# PCBv1.net
KiCad netlist of a schematic drawn in EAGLE
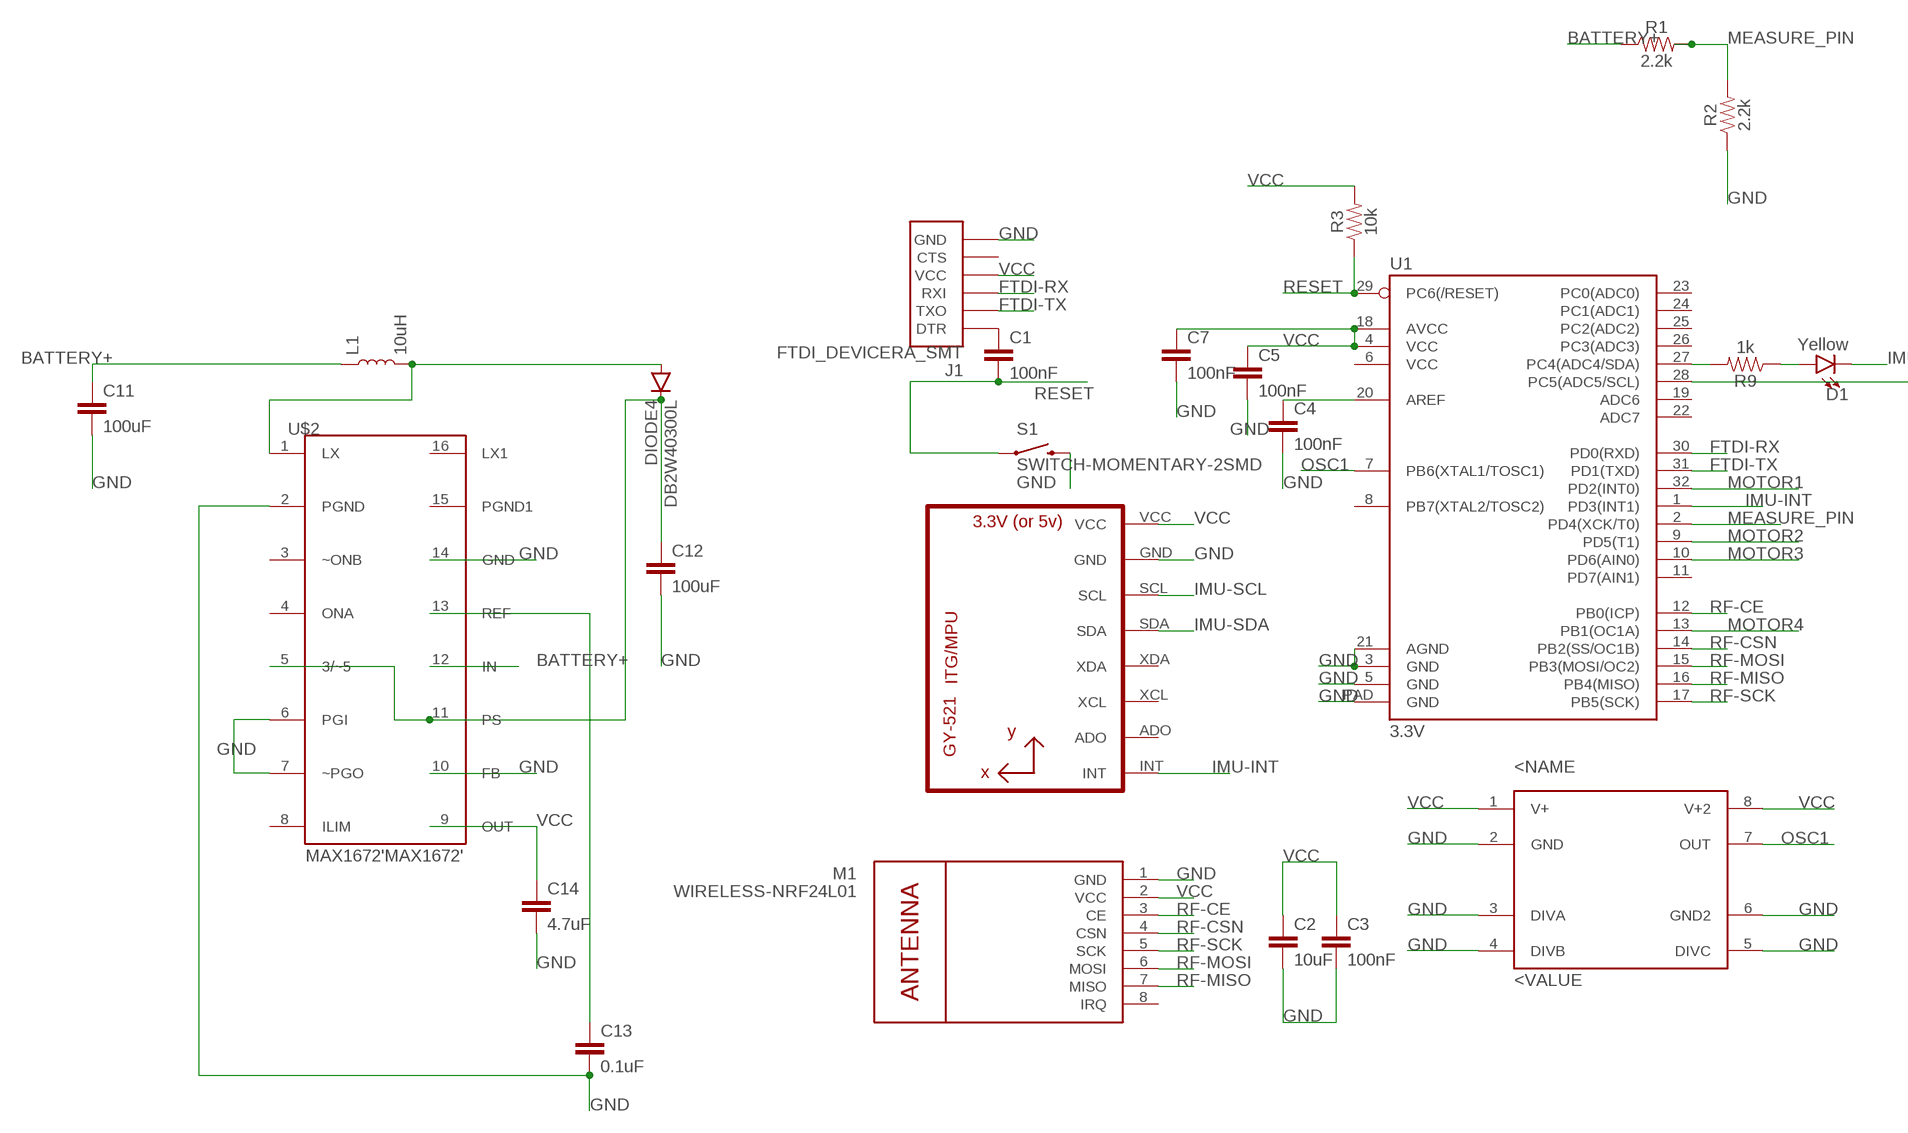
[diagram p0: schematic, sheet 1, part 1 of 2]
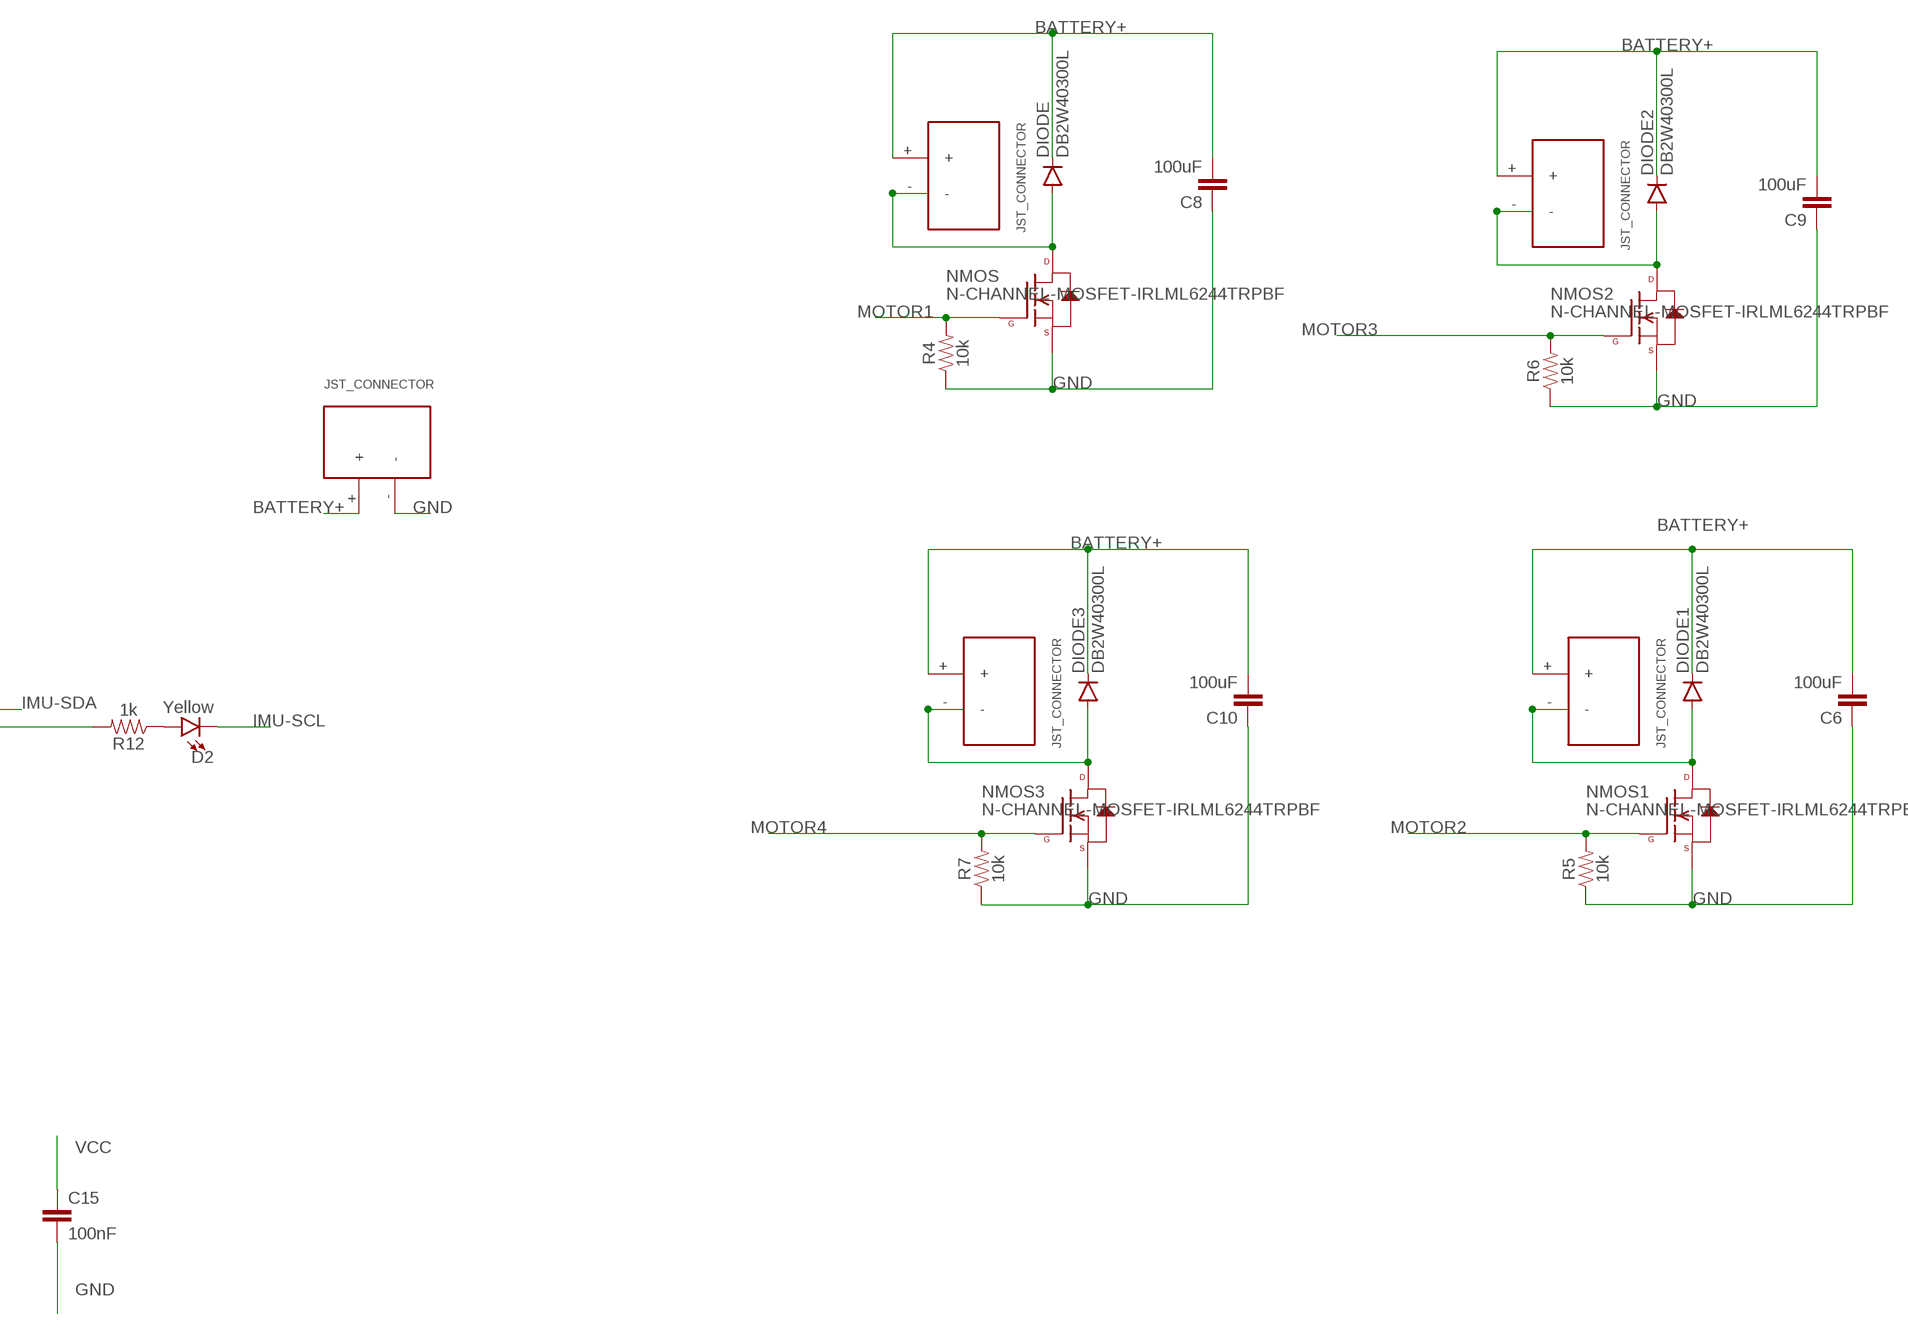
[diagram p1: schematic, sheet 1, part 2 of 2]

(export (version "E")
  (design (tool "Eeschema 10.0.6"))
  (components
    (comp (ref "C1")
      (value "100nF")
      (footprint "eagle-import:0603-CAP")
      (libsource (lib "eagle-import") (part "0.1UF-25V(+80/-20%)(0603)"))
    )
    (comp (ref "C2")
      (value "10uF")
      (footprint "eagle-import:0603-CAP")
      (libsource (lib "eagle-import") (part "CAP0603-CAP"))
    )
    (comp (ref "C3")
      (value "100nF")
      (footprint "eagle-import:0603-CAP")
      (libsource (lib "eagle-import") (part "CAP0603-CAP"))
    )
    (comp (ref "C4")
      (value "100nF")
      (footprint "eagle-import:0603-CAP")
      (libsource (lib "eagle-import") (part "CAP0603-CAP"))
    )
    (comp (ref "C5")
      (value "100nF")
      (footprint "eagle-import:0603-CAP")
      (libsource (lib "eagle-import") (part "CAP0603-CAP"))
    )
    (comp (ref "C6")
      (value "100uF")
      (footprint "eagle-import:0603-CAP")
      (libsource (lib "eagle-import") (part "CAP0603-CAP"))
    )
    (comp (ref "C7")
      (value "100nF")
      (footprint "eagle-import:0603-CAP")
      (libsource (lib "eagle-import") (part "CAP0603-CAP"))
    )
    (comp (ref "C8")
      (value "100uF")
      (footprint "eagle-import:0603-CAP")
      (libsource (lib "eagle-import") (part "CAP0603-CAP"))
    )
    (comp (ref "C9")
      (value "100uF")
      (footprint "eagle-import:0603-CAP")
      (libsource (lib "eagle-import") (part "CAP0603-CAP"))
    )
    (comp (ref "C10")
      (value "100uF")
      (footprint "eagle-import:0603-CAP")
      (libsource (lib "eagle-import") (part "CAP0603-CAP"))
    )
    (comp (ref "C11")
      (value "100uF")
      (footprint "eagle-import:0603-CAP")
      (libsource (lib "eagle-import") (part "CAP0603-CAP"))
    )
    (comp (ref "C12")
      (value "100uF")
      (footprint "eagle-import:0603-CAP")
      (libsource (lib "eagle-import") (part "CAP0603-CAP"))
    )
    (comp (ref "C13")
      (value "0.1uF")
      (footprint "eagle-import:0603-CAP")
      (libsource (lib "eagle-import") (part "CAP0603-CAP"))
    )
    (comp (ref "C14")
      (value "4.7uF")
      (footprint "eagle-import:0603-CAP")
      (libsource (lib "eagle-import") (part "CAP0603-CAP"))
    )
    (comp (ref "C15")
      (value "100nF")
      (footprint "eagle-import:0603-CAP")
      (libsource (lib "eagle-import") (part "0.1UF-25V(+80/-20%)(0603)"))
    )
    (comp (ref "D1")
      (value "Yellow")
      (footprint "eagle-import:LED-1206")
      (libsource (lib "eagle-import") (part "LED-YELLOWLILYPAD"))
    )
    (comp (ref "D2")
      (value "Yellow")
      (footprint "eagle-import:LED-1206")
      (libsource (lib "eagle-import") (part "LED-YELLOWLILYPAD"))
    )
    (comp (ref "DIODE")
      (value "DB2W40300L")
      (footprint "eagle-import:MINI2-F3-B")
      (libsource (lib "eagle-import") (part "DB2W40300L"))
    )
    (comp (ref "DIODE1")
      (value "DB2W40300L")
      (footprint "eagle-import:MINI2-F3-B")
      (libsource (lib "eagle-import") (part "DB2W40300L"))
    )
    (comp (ref "DIODE2")
      (value "DB2W40300L")
      (footprint "eagle-import:MINI2-F3-B")
      (libsource (lib "eagle-import") (part "DB2W40300L"))
    )
    (comp (ref "DIODE3")
      (value "DB2W40300L")
      (footprint "eagle-import:MINI2-F3-B")
      (libsource (lib "eagle-import") (part "DB2W40300L"))
    )
    (comp (ref "DIODE4")
      (value "DB2W40300L")
      (footprint "eagle-import:MINI2-F3-B")
      (libsource (lib "eagle-import") (part "DB2W40300L"))
    )
    (comp (ref "J1")
      (value "FTDI_DEVICERA_SMT")
      (footprint "eagle-import:FTDI_DEVICE_RA_SMT")
      (libsource (lib "eagle-import") (part "FTDI_DEVICERA_SMT"))
    )
    (comp (ref "L1")
      (value "10uH")
      (footprint "eagle-import:0603")
      (libsource (lib "eagle-import") (part "INDUCTOR-0603-33NH"))
    )
    (comp (ref "M1")
      (value "WIRELESS-NRF24L01")
      (footprint "eagle-import:WIRELESS-NRF24L01")
      (libsource (lib "eagle-import") (part "WIRELESS-NRF24L01"))
    )
    (comp (ref "MOTOR")
      (value "JST_CONNECTOR_FEMALE")
      (footprint "eagle-import:JST_CONNECTOR_FEMALE")
      (libsource (lib "eagle-import") (part "JST_CONNECTOR_FEMALE"))
    )
    (comp (ref "MOTOR1")
      (value "JST_CONNECTOR_FEMALE")
      (footprint "eagle-import:JST_CONNECTOR_FEMALE")
      (libsource (lib "eagle-import") (part "JST_CONNECTOR_FEMALE"))
    )
    (comp (ref "MOTOR2")
      (value "JST_CONNECTOR_FEMALE")
      (footprint "eagle-import:JST_CONNECTOR_FEMALE")
      (libsource (lib "eagle-import") (part "JST_CONNECTOR_FEMALE"))
    )
    (comp (ref "MOTOR3")
      (value "JST_CONNECTOR_FEMALE")
      (footprint "eagle-import:JST_CONNECTOR_FEMALE")
      (libsource (lib "eagle-import") (part "JST_CONNECTOR_FEMALE"))
    )
    (comp (ref "NMOS")
      (value "N-CHANNEL-MOSFET-IRLML6244TRPBF")
      (footprint "eagle-import:SOT23-3")
      (libsource (lib "eagle-import") (part "N-CHANNEL-MOSFET-IRLML6244TRPBF"))
    )
    (comp (ref "NMOS1")
      (value "N-CHANNEL-MOSFET-IRLML6244TRPBF")
      (footprint "eagle-import:SOT23-3")
      (libsource (lib "eagle-import") (part "N-CHANNEL-MOSFET-IRLML6244TRPBF"))
    )
    (comp (ref "NMOS2")
      (value "N-CHANNEL-MOSFET-IRLML6244TRPBF")
      (footprint "eagle-import:SOT23-3")
      (libsource (lib "eagle-import") (part "N-CHANNEL-MOSFET-IRLML6244TRPBF"))
    )
    (comp (ref "NMOS3")
      (value "N-CHANNEL-MOSFET-IRLML6244TRPBF")
      (footprint "eagle-import:SOT23-3")
      (libsource (lib "eagle-import") (part "N-CHANNEL-MOSFET-IRLML6244TRPBF"))
    )
    (comp (ref "R1")
      (value "2.2k")
      (footprint "eagle-import:0603")
      (libsource (lib "eagle-import") (part "2.2KOHM-0603-1/10W-1%"))
    )
    (comp (ref "R2")
      (value "2.2k")
      (footprint "eagle-import:0603")
      (libsource (lib "eagle-import") (part "2.2KOHM-0603-1/10W-1%"))
    )
    (comp (ref "R3")
      (value "10k")
      (footprint "eagle-import:0603")
      (libsource (lib "eagle-import") (part "2.2KOHM-0603-1/10W-1%"))
    )
    (comp (ref "R4")
      (value "10k")
      (footprint "eagle-import:0603")
      (libsource (lib "eagle-import") (part "2.2KOHM-0603-1/10W-1%"))
    )
    (comp (ref "R5")
      (value "10k")
      (footprint "eagle-import:0603")
      (libsource (lib "eagle-import") (part "2.2KOHM-0603-1/10W-1%"))
    )
    (comp (ref "R6")
      (value "10k")
      (footprint "eagle-import:0603")
      (libsource (lib "eagle-import") (part "2.2KOHM-0603-1/10W-1%"))
    )
    (comp (ref "R7")
      (value "10k")
      (footprint "eagle-import:0603")
      (libsource (lib "eagle-import") (part "2.2KOHM-0603-1/10W-1%"))
    )
    (comp (ref "R9")
      (value "1k")
      (footprint "eagle-import:0603")
      (libsource (lib "eagle-import") (part "2.2KOHM-0603-1/10W-1%"))
    )
    (comp (ref "R12")
      (value "1k")
      (footprint "eagle-import:0603")
      (libsource (lib "eagle-import") (part "2.2KOHM-0603-1/10W-1%"))
    )
    (comp (ref "S1")
      (value "SWITCH-MOMENTARY-2SMD")
      (footprint "eagle-import:TACTILE-SWITCH-SMD")
      (libsource (lib "eagle-import") (part "SWITCH-MOMENTARY-2SMD"))
    )
    (comp (ref "U$1")
      (value "JST_CONNECTOR_FEMALE")
      (footprint "eagle-import:JST_CONNECTOR_FEMALE")
      (libsource (lib "eagle-import") (part "JST_CONNECTOR_FEMALE"))
    )
    (comp (ref "U$2")
      (value "MAX1672'MAX1672'")
      (footprint "eagle-import:21-0055H_16")
      (libsource (lib "eagle-import") (part "MAX1672'MAX1672'"))
    )
    (comp (ref "U$3")
      (value "LTC6930CMS8-8.19LTC6930CMS8-8.19")
      (footprint "eagle-import:SOP65P490X110-8N")
      (libsource (lib "eagle-import") (part "LTC6930CMS8-8.19LTC6930CMS8-8.19"))
    )
    (comp (ref "U1")
      (value "3.3V")
      (footprint "eagle-import:MLF32-PAD")
      (libsource (lib "eagle-import") (part "ATMEGA328P_MLFMLF32"))
    )
    (comp (ref "U2")
      (value "GY-521MPU6050")
      (footprint "eagle-import:GY-521")
      (libsource (lib "eagle-import") (part "GY-521MPU6050"))
    )
  )
  (nets
    (net (code "1") (name "BATTERY+") (class "Default")
      (node (ref "C10") (pin "2") (pinfunction "2_2") (pintype "passive"))
      (node (ref "C11") (pin "1") (pinfunction "1_1") (pintype "passive"))
      (node (ref "C6") (pin "2") (pinfunction "2_2") (pintype "passive"))
      (node (ref "C8") (pin "2") (pinfunction "2_2") (pintype "passive"))
      (node (ref "C9") (pin "2") (pinfunction "2_2") (pintype "passive"))
      (node (ref "DIODE") (pin "NEG") (pinfunction "GPIN_NEG") (pintype "passive"))
      (node (ref "DIODE1") (pin "NEG") (pinfunction "GPIN_NEG") (pintype "passive"))
      (node (ref "DIODE2") (pin "NEG") (pinfunction "GPIN_NEG") (pintype "passive"))
      (node (ref "DIODE3") (pin "NEG") (pinfunction "GPIN_NEG") (pintype "passive"))
      (node (ref "L1") (pin "1") (pinfunction "1_1") (pintype "passive"))
      (node (ref "MOTOR") (pin "+") (pinfunction "+_+") (pintype "bidirectional"))
      (node (ref "MOTOR1") (pin "+") (pinfunction "+_+") (pintype "bidirectional"))
      (node (ref "MOTOR2") (pin "+") (pinfunction "+_+") (pintype "bidirectional"))
      (node (ref "MOTOR3") (pin "+") (pinfunction "+_+") (pintype "bidirectional"))
      (node (ref "R1") (pin "1") (pinfunction "1_1") (pintype "passive"))
      (node (ref "U$1") (pin "+") (pinfunction "+_+") (pintype "bidirectional"))
      (node (ref "U$2") (pin "12") (pinfunction "IN_12") (pintype "bidirectional"))
    )
    (net (code "2") (name "FTDI-RX") (class "Default")
      (node (ref "J1") (pin "3") (pinfunction "RXI_3") (pintype "bidirectional"))
      (node (ref "U1") (pin "30") (pinfunction "PD0(RXD)_30") (pintype "bidirectional"))
    )
    (net (code "3") (name "FTDI-TX") (class "Default")
      (node (ref "J1") (pin "2") (pinfunction "TXO_2") (pintype "bidirectional"))
      (node (ref "U1") (pin "31") (pinfunction "PD1(TXD)_31") (pintype "bidirectional"))
    )
    (net (code "4") (name "GND") (class "Default")
      (node (ref "C10") (pin "1") (pinfunction "1_1") (pintype "passive"))
      (node (ref "C11") (pin "2") (pinfunction "2_2") (pintype "passive"))
      (node (ref "C12") (pin "2") (pinfunction "2_2") (pintype "passive"))
      (node (ref "C13") (pin "2") (pinfunction "2_2") (pintype "passive"))
      (node (ref "C14") (pin "2") (pinfunction "2_2") (pintype "passive"))
      (node (ref "C15") (pin "2") (pinfunction "2_2") (pintype "passive"))
      (node (ref "C2") (pin "2") (pinfunction "2_2") (pintype "passive"))
      (node (ref "C3") (pin "2") (pinfunction "2_2") (pintype "passive"))
      (node (ref "C4") (pin "2") (pinfunction "2_2") (pintype "passive"))
      (node (ref "C5") (pin "2") (pinfunction "2_2") (pintype "passive"))
      (node (ref "C6") (pin "1") (pinfunction "1_1") (pintype "passive"))
      (node (ref "C7") (pin "2") (pinfunction "2_2") (pintype "passive"))
      (node (ref "C8") (pin "1") (pinfunction "1_1") (pintype "passive"))
      (node (ref "C9") (pin "1") (pinfunction "1_1") (pintype "passive"))
      (node (ref "J1") (pin "6") (pinfunction "GND_6") (pintype "bidirectional"))
      (node (ref "M1") (pin "1") (pinfunction "GND_1") (pintype "power_in"))
      (node (ref "NMOS") (pin "2") (pinfunction "S_2") (pintype "passive"))
      (node (ref "NMOS1") (pin "2") (pinfunction "S_2") (pintype "passive"))
      (node (ref "NMOS2") (pin "2") (pinfunction "S_2") (pintype "passive"))
      (node (ref "NMOS3") (pin "2") (pinfunction "S_2") (pintype "passive"))
      (node (ref "R2") (pin "1") (pinfunction "1_1") (pintype "passive"))
      (node (ref "R4") (pin "1") (pinfunction "1_1") (pintype "passive"))
      (node (ref "R5") (pin "1") (pinfunction "1_1") (pintype "passive"))
      (node (ref "R6") (pin "1") (pinfunction "1_1") (pintype "passive"))
      (node (ref "R7") (pin "1") (pinfunction "1_1") (pintype "passive"))
      (node (ref "S1") (pin "3") (pinfunction "2_3") (pintype "passive"))
      (node (ref "U$1") (pin "-") (pinfunction "-_-") (pintype "bidirectional"))
      (node (ref "U$2") (pin "10") (pinfunction "FB_10") (pintype "bidirectional"))
      (node (ref "U$2") (pin "14") (pinfunction "GND_14") (pintype "bidirectional"))
      (node (ref "U$2") (pin "2") (pinfunction "PGND_2") (pintype "bidirectional"))
      (node (ref "U$2") (pin "6") (pinfunction "PGI_6") (pintype "bidirectional"))
      (node (ref "U$2") (pin "7") (pinfunction "~{PGO}_7") (pintype "bidirectional"))
      (node (ref "U$3") (pin "2") (pinfunction "GND_2") (pintype "bidirectional"))
      (node (ref "U$3") (pin "3") (pinfunction "DIVA_3") (pintype "bidirectional"))
      (node (ref "U$3") (pin "4") (pinfunction "DIVB_4") (pintype "bidirectional"))
      (node (ref "U$3") (pin "5") (pinfunction "DIVC_5") (pintype "bidirectional"))
      (node (ref "U$3") (pin "6") (pinfunction "GND2_6") (pintype "bidirectional"))
      (node (ref "U1") (pin "21") (pinfunction "AGND_21") (pintype "bidirectional"))
      (node (ref "U1") (pin "3") (pinfunction "GND_3") (pintype "bidirectional"))
      (node (ref "U1") (pin "5") (pinfunction "GND_5") (pintype "bidirectional"))
      (node (ref "U1") (pin "PAD") (pinfunction "GND_PAD") (pintype "bidirectional"))
      (node (ref "U2") (pin "GND") (pinfunction "GND_GND") (pintype "bidirectional"))
    )
    (net (code "5") (name "IMU-INT") (class "Default")
      (node (ref "U1") (pin "1") (pinfunction "PD3(INT1)_1") (pintype "bidirectional"))
      (node (ref "U2") (pin "INT") (pinfunction "INT_INT") (pintype "bidirectional"))
    )
    (net (code "6") (name "IMU-SCL") (class "Default")
      (node (ref "D2") (pin "C") (pinfunction "C_C") (pintype "passive"))
      (node (ref "U2") (pin "SCL") (pinfunction "SCL_SCL") (pintype "bidirectional"))
    )
    (net (code "7") (name "IMU-SDA") (class "Default")
      (node (ref "D1") (pin "C") (pinfunction "C_C") (pintype "passive"))
      (node (ref "U2") (pin "SDA") (pinfunction "SDA_SDA") (pintype "bidirectional"))
    )
    (net (code "8") (name "MEASURE_PIN") (class "Default")
      (node (ref "R1") (pin "2") (pinfunction "2_2") (pintype "passive"))
      (node (ref "R2") (pin "2") (pinfunction "2_2") (pintype "passive"))
      (node (ref "U1") (pin "2") (pinfunction "PD4(XCK/T0)_2") (pintype "bidirectional"))
    )
    (net (code "9") (name "MOTOR1") (class "Default")
      (node (ref "NMOS") (pin "1") (pinfunction "G_1") (pintype "passive"))
      (node (ref "R4") (pin "2") (pinfunction "2_2") (pintype "passive"))
      (node (ref "U1") (pin "32") (pinfunction "PD2(INT0)_32") (pintype "bidirectional"))
    )
    (net (code "10") (name "MOTOR2") (class "Default")
      (node (ref "NMOS1") (pin "1") (pinfunction "G_1") (pintype "passive"))
      (node (ref "R5") (pin "2") (pinfunction "2_2") (pintype "passive"))
      (node (ref "U1") (pin "9") (pinfunction "PD5(T1)_9") (pintype "bidirectional"))
    )
    (net (code "11") (name "MOTOR3") (class "Default")
      (node (ref "NMOS2") (pin "1") (pinfunction "G_1") (pintype "passive"))
      (node (ref "R6") (pin "2") (pinfunction "2_2") (pintype "passive"))
      (node (ref "U1") (pin "10") (pinfunction "PD6(AIN0)_10") (pintype "bidirectional"))
    )
    (net (code "12") (name "MOTOR4") (class "Default")
      (node (ref "NMOS3") (pin "1") (pinfunction "G_1") (pintype "passive"))
      (node (ref "R7") (pin "2") (pinfunction "2_2") (pintype "passive"))
      (node (ref "U1") (pin "13") (pinfunction "PB1(OC1A)_13") (pintype "bidirectional"))
    )
    (net (code "13") (name "Net-(D1-PadA)") (class "Default")
      (node (ref "D1") (pin "A") (pinfunction "A_A") (pintype "passive"))
      (node (ref "R9") (pin "1") (pinfunction "1_1") (pintype "passive"))
    )
    (net (code "14") (name "Net-(D2-PadA)") (class "Default")
      (node (ref "D2") (pin "A") (pinfunction "A_A") (pintype "passive"))
      (node (ref "R12") (pin "1") (pinfunction "1_1") (pintype "passive"))
    )
    (net (code "15") (name "Net-(DIODE-PPIN)") (class "Default")
      (node (ref "DIODE") (pin "POS") (pinfunction "PPIN_POS") (pintype "passive"))
      (node (ref "MOTOR") (pin "-") (pinfunction "-_-") (pintype "bidirectional"))
      (node (ref "NMOS") (pin "3") (pinfunction "D_3") (pintype "passive"))
    )
    (net (code "16") (name "Net-(DIODE1-PPIN)") (class "Default")
      (node (ref "DIODE1") (pin "POS") (pinfunction "PPIN_POS") (pintype "passive"))
      (node (ref "MOTOR1") (pin "-") (pinfunction "-_-") (pintype "bidirectional"))
      (node (ref "NMOS1") (pin "3") (pinfunction "D_3") (pintype "passive"))
    )
    (net (code "17") (name "Net-(DIODE2-PPIN)") (class "Default")
      (node (ref "DIODE2") (pin "POS") (pinfunction "PPIN_POS") (pintype "passive"))
      (node (ref "MOTOR2") (pin "-") (pinfunction "-_-") (pintype "bidirectional"))
      (node (ref "NMOS2") (pin "3") (pinfunction "D_3") (pintype "passive"))
    )
    (net (code "18") (name "Net-(DIODE3-PPIN)") (class "Default")
      (node (ref "DIODE3") (pin "POS") (pinfunction "PPIN_POS") (pintype "passive"))
      (node (ref "MOTOR3") (pin "-") (pinfunction "-_-") (pintype "bidirectional"))
      (node (ref "NMOS3") (pin "3") (pinfunction "D_3") (pintype "passive"))
    )
    (net (code "19") (name "Net-(DIODE4-GPIN)") (class "Default")
      (node (ref "C12") (pin "1") (pinfunction "1_1") (pintype "passive"))
      (node (ref "DIODE4") (pin "NEG") (pinfunction "GPIN_NEG") (pintype "passive"))
      (node (ref "U$2") (pin "11") (pinfunction "PS_11") (pintype "bidirectional"))
      (node (ref "U$2") (pin "5") (pinfunction "3/~{5}_5") (pintype "bidirectional"))
    )
    (net (code "20") (name "Net-(DIODE4-PPIN)") (class "Default")
      (node (ref "DIODE4") (pin "POS") (pinfunction "PPIN_POS") (pintype "passive"))
      (node (ref "L1") (pin "2") (pinfunction "2_2") (pintype "passive"))
      (node (ref "U$2") (pin "1") (pinfunction "LX_1") (pintype "bidirectional"))
    )
    (net (code "21") (name "Net-(J1-DTR)") (class "Default")
      (node (ref "C1") (pin "1") (pinfunction "1_1") (pintype "passive"))
      (node (ref "J1") (pin "1") (pinfunction "DTR_1") (pintype "bidirectional"))
    )
    (net (code "22") (name "Net-(U$2-REF)") (class "Default")
      (node (ref "C13") (pin "1") (pinfunction "1_1") (pintype "passive"))
      (node (ref "U$2") (pin "13") (pinfunction "REF_13") (pintype "bidirectional"))
    )
    (net (code "23") (name "Net-(U1-AREF)") (class "Default")
      (node (ref "C4") (pin "1") (pinfunction "1_1") (pintype "passive"))
      (node (ref "U1") (pin "20") (pinfunction "AREF_20") (pintype "bidirectional"))
    )
    (net (code "24") (name "Net-(U1-PC4(ADC4{slash}SDA))") (class "Default")
      (node (ref "R9") (pin "2") (pinfunction "2_2") (pintype "passive"))
      (node (ref "U1") (pin "27") (pinfunction "PC4(ADC4/SDA)_27") (pintype "bidirectional"))
    )
    (net (code "25") (name "Net-(U1-PC5(ADC5{slash}SCL))") (class "Default")
      (node (ref "R12") (pin "2") (pinfunction "2_2") (pintype "passive"))
      (node (ref "U1") (pin "28") (pinfunction "PC5(ADC5/SCL)_28") (pintype "bidirectional"))
    )
    (net (code "26") (name "OSC1") (class "Default")
      (node (ref "U$3") (pin "7") (pinfunction "OUT_7") (pintype "bidirectional"))
      (node (ref "U1") (pin "7") (pinfunction "PB6(XTAL1/TOSC1)_7") (pintype "bidirectional"))
    )
    (net (code "27") (name "RESET") (class "Default")
      (node (ref "C1") (pin "2") (pinfunction "2_2") (pintype "passive"))
      (node (ref "R3") (pin "1") (pinfunction "1_1") (pintype "passive"))
      (node (ref "S1") (pin "1") (pinfunction "1_1") (pintype "passive"))
      (node (ref "U1") (pin "29") (pinfunction "PC6(/RESET)_29") (pintype "bidirectional"))
    )
    (net (code "28") (name "RF-CE") (class "Default")
      (node (ref "M1") (pin "3") (pinfunction "CE_3") (pintype "bidirectional"))
      (node (ref "U1") (pin "12") (pinfunction "PB0(ICP)_12") (pintype "bidirectional"))
    )
    (net (code "29") (name "RF-CSN") (class "Default")
      (node (ref "M1") (pin "4") (pinfunction "CSN_4") (pintype "bidirectional"))
      (node (ref "U1") (pin "14") (pinfunction "PB2(SS/OC1B)_14") (pintype "bidirectional"))
    )
    (net (code "30") (name "RF-MISO") (class "Default")
      (node (ref "M1") (pin "7") (pinfunction "MISO_7") (pintype "bidirectional"))
      (node (ref "U1") (pin "16") (pinfunction "PB4(MISO)_16") (pintype "bidirectional"))
    )
    (net (code "31") (name "RF-MOSI") (class "Default")
      (node (ref "M1") (pin "6") (pinfunction "MOSI_6") (pintype "bidirectional"))
      (node (ref "U1") (pin "15") (pinfunction "PB3(MOSI/OC2)_15") (pintype "bidirectional"))
    )
    (net (code "32") (name "RF-SCK") (class "Default")
      (node (ref "M1") (pin "5") (pinfunction "SCK_5") (pintype "bidirectional"))
      (node (ref "U1") (pin "17") (pinfunction "PB5(SCK)_17") (pintype "bidirectional"))
    )
    (net (code "33") (name "VCC") (class "Default")
      (node (ref "C14") (pin "1") (pinfunction "1_1") (pintype "passive"))
      (node (ref "C15") (pin "1") (pinfunction "1_1") (pintype "passive"))
      (node (ref "C2") (pin "1") (pinfunction "1_1") (pintype "passive"))
      (node (ref "C3") (pin "1") (pinfunction "1_1") (pintype "passive"))
      (node (ref "C5") (pin "1") (pinfunction "1_1") (pintype "passive"))
      (node (ref "C7") (pin "1") (pinfunction "1_1") (pintype "passive"))
      (node (ref "J1") (pin "4") (pinfunction "VCC_4") (pintype "bidirectional"))
      (node (ref "M1") (pin "2") (pinfunction "VCC_2") (pintype "power_in"))
      (node (ref "R3") (pin "2") (pinfunction "2_2") (pintype "passive"))
      (node (ref "U$2") (pin "9") (pinfunction "OUT_9") (pintype "bidirectional"))
      (node (ref "U$3") (pin "1") (pinfunction "V+_1") (pintype "bidirectional"))
      (node (ref "U$3") (pin "8") (pinfunction "V+2_8") (pintype "bidirectional"))
      (node (ref "U1") (pin "18") (pinfunction "AVCC_18") (pintype "bidirectional"))
      (node (ref "U1") (pin "4") (pinfunction "VCC_4") (pintype "bidirectional"))
      (node (ref "U2") (pin "VCC") (pinfunction "VCC_VCC") (pintype "bidirectional"))
    )
    (net (code "34") (name "unconnected-(J1-CTS-Pad5)") (class "Default")
      (node (ref "J1") (pin "5") (pinfunction "CTS_5") (pintype "bidirectional"))
    )
    (net (code "35") (name "unconnected-(M1-IRQ-Pad8)") (class "Default")
      (node (ref "M1") (pin "8") (pinfunction "IRQ_8") (pintype "bidirectional"))
    )
    (net (code "36") (name "unconnected-(U$2-ILIM-Pad8)") (class "Default")
      (node (ref "U$2") (pin "8") (pinfunction "ILIM_8") (pintype "bidirectional"))
    )
    (net (code "37") (name "unconnected-(U$2-LX1-Pad16)") (class "Default")
      (node (ref "U$2") (pin "16") (pinfunction "LX1_16") (pintype "bidirectional"))
    )
    (net (code "38") (name "unconnected-(U$2-ONA-Pad4)") (class "Default")
      (node (ref "U$2") (pin "4") (pinfunction "ONA_4") (pintype "bidirectional"))
    )
    (net (code "39") (name "unconnected-(U$2-PGND1-Pad15)") (class "Default")
      (node (ref "U$2") (pin "15") (pinfunction "PGND1_15") (pintype "bidirectional"))
    )
    (net (code "40") (name "unconnected-(U$2-~{ONB}-Pad3)") (class "Default")
      (node (ref "U$2") (pin "3") (pinfunction "~{ONB}_3") (pintype "bidirectional"))
    )
    (net (code "41") (name "unconnected-(U1-ADC6-Pad19)") (class "Default")
      (node (ref "U1") (pin "19") (pinfunction "ADC6_19") (pintype "bidirectional"))
    )
    (net (code "42") (name "unconnected-(U1-ADC7-Pad22)") (class "Default")
      (node (ref "U1") (pin "22") (pinfunction "ADC7_22") (pintype "bidirectional"))
    )
    (net (code "43") (name "unconnected-(U1-PB7(XTAL2{slash}TOSC2)-Pad8)") (class "Default")
      (node (ref "U1") (pin "8") (pinfunction "PB7(XTAL2/TOSC2)_8") (pintype "bidirectional"))
    )
    (net (code "44") (name "unconnected-(U1-PC0(ADC0)-Pad23)") (class "Default")
      (node (ref "U1") (pin "23") (pinfunction "PC0(ADC0)_23") (pintype "bidirectional"))
    )
    (net (code "45") (name "unconnected-(U1-PC1(ADC1)-Pad24)") (class "Default")
      (node (ref "U1") (pin "24") (pinfunction "PC1(ADC1)_24") (pintype "bidirectional"))
    )
    (net (code "46") (name "unconnected-(U1-PC2(ADC2)-Pad25)") (class "Default")
      (node (ref "U1") (pin "25") (pinfunction "PC2(ADC2)_25") (pintype "bidirectional"))
    )
    (net (code "47") (name "unconnected-(U1-PC3(ADC3)-Pad26)") (class "Default")
      (node (ref "U1") (pin "26") (pinfunction "PC3(ADC3)_26") (pintype "bidirectional"))
    )
    (net (code "48") (name "unconnected-(U1-PD7(AIN1)-Pad11)") (class "Default")
      (node (ref "U1") (pin "11") (pinfunction "PD7(AIN1)_11") (pintype "bidirectional"))
    )
    (net (code "49") (name "unconnected-(U1-VCC-Pad6)") (class "Default")
      (node (ref "U1") (pin "6") (pinfunction "VCC_6") (pintype "bidirectional"))
    )
    (net (code "50") (name "unconnected-(U2-PadADO)") (class "Default")
      (node (ref "U2") (pin "ADO") (pinfunction "ADO_ADO") (pintype "bidirectional"))
    )
    (net (code "51") (name "unconnected-(U2-PadXCL)") (class "Default")
      (node (ref "U2") (pin "XCL") (pinfunction "XCL_XCL") (pintype "bidirectional"))
    )
    (net (code "52") (name "unconnected-(U2-PadXDA)") (class "Default")
      (node (ref "U2") (pin "XDA") (pinfunction "XDA_XDA") (pintype "bidirectional"))
    )
  )
)
